# B166X.net
KiCad netlist of a schematic drawn in EAGLE
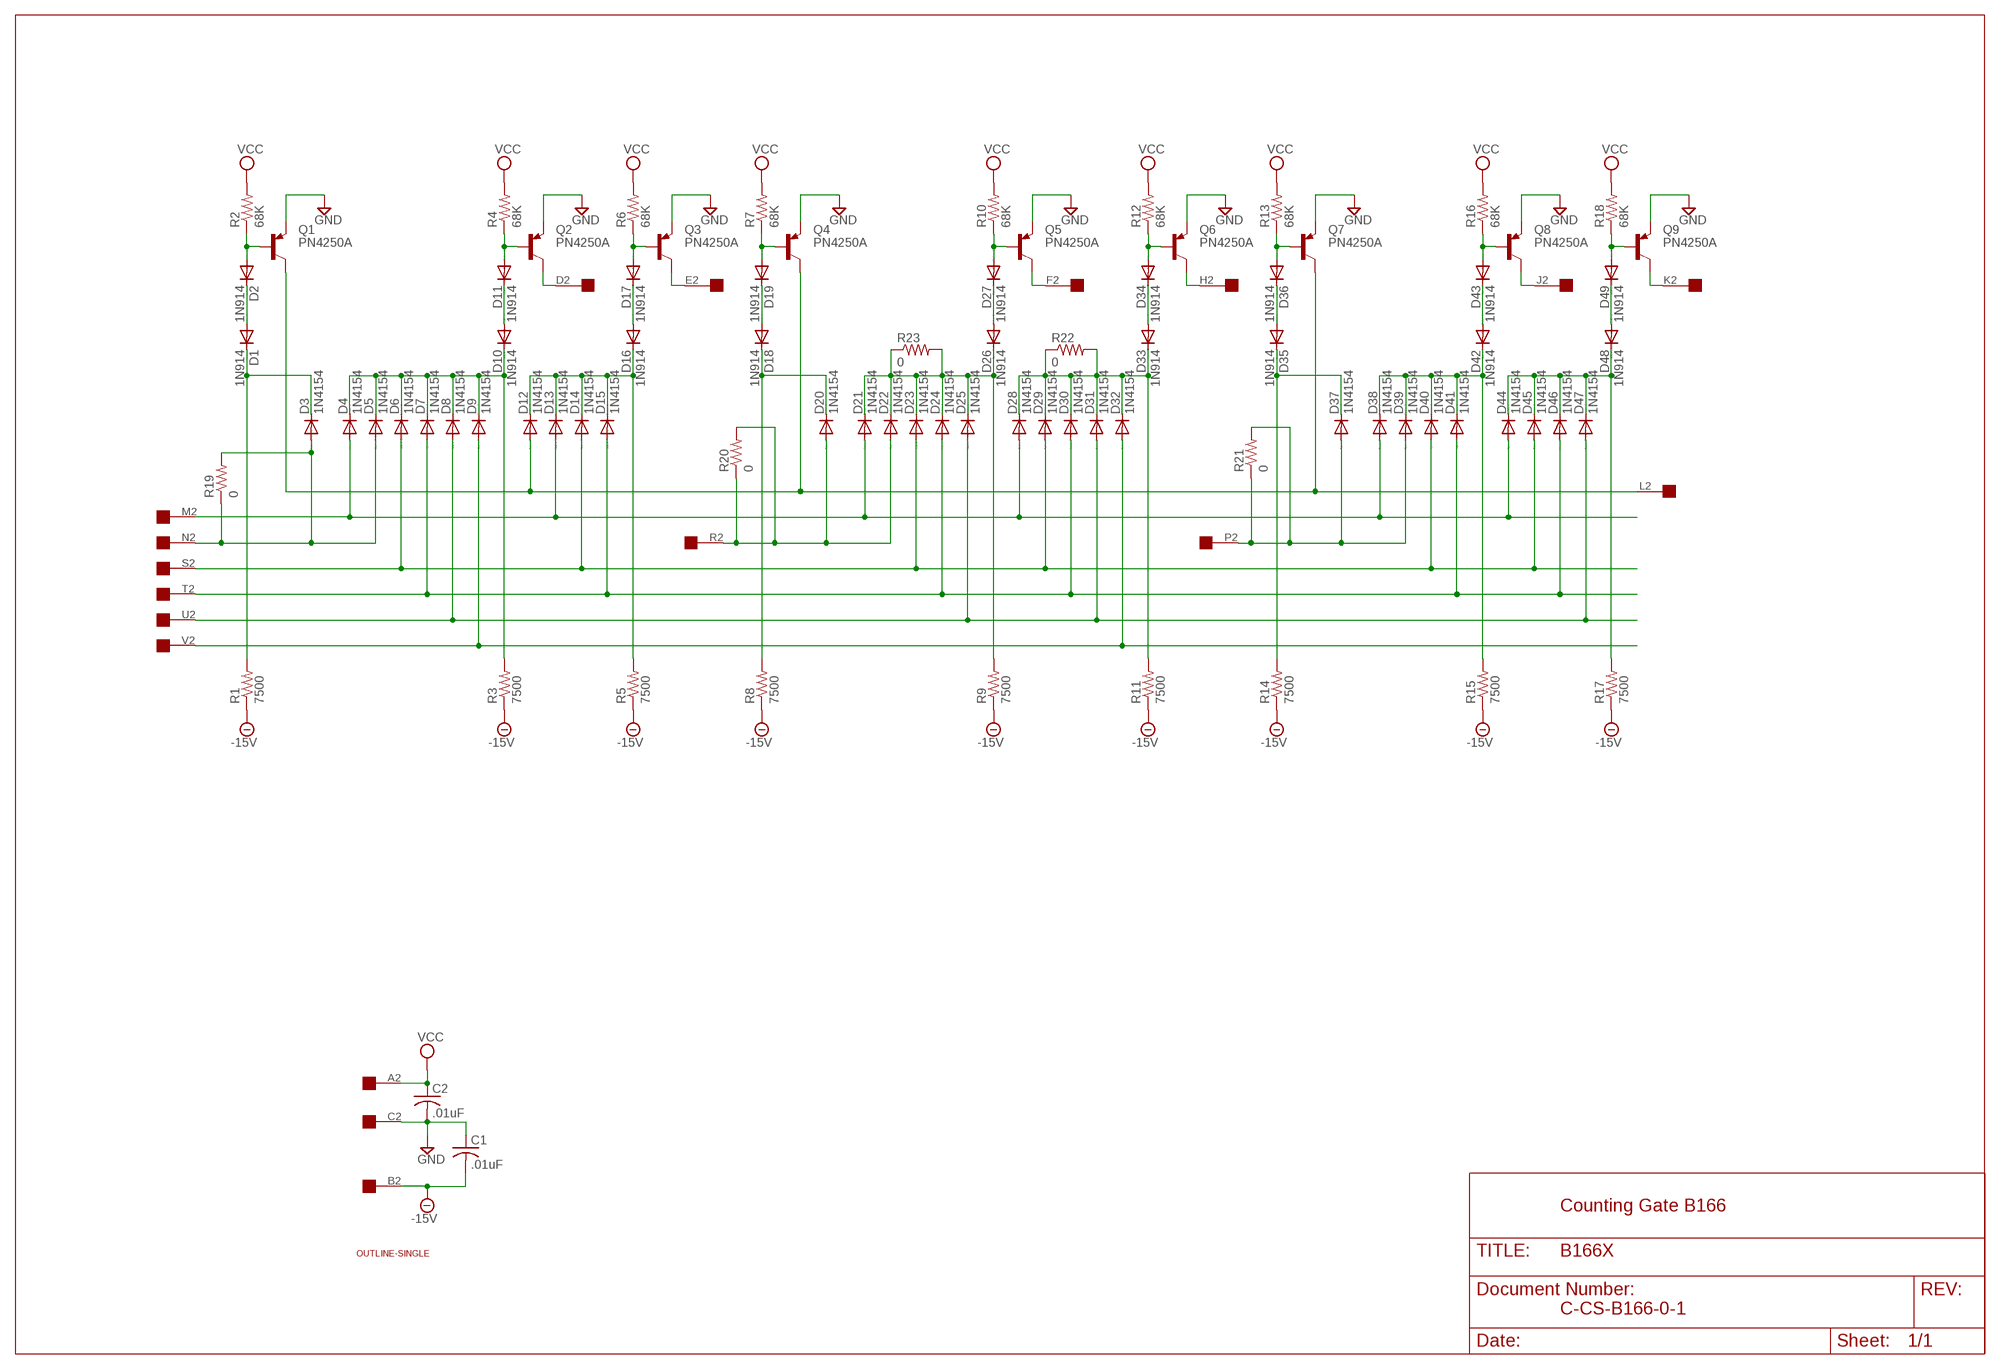
[diagram p0: schematic, sheet 1]

(export (version "E")
  (design (tool "Eeschema 10.0.6"))
  (components
    (comp (ref "C1")
      (value ".01uF")
      (footprint "eagle-import:C063-025X075")
      (libsource (lib "eagle-import") (part "C-US"))
    )
    (comp (ref "C2")
      (value ".01uF")
      (footprint "eagle-import:C063-025X075")
      (libsource (lib "eagle-import") (part "C-US"))
    )
    (comp (ref "D1")
      (value "1N914")
      (footprint "eagle-import:DO35-10")
      (libsource (lib "eagle-import") (part "DIODE-DO35-10"))
    )
    (comp (ref "D2")
      (value "1N914")
      (footprint "eagle-import:DO35-10")
      (libsource (lib "eagle-import") (part "DIODE-DO35-10"))
    )
    (comp (ref "D3")
      (value "1N4154")
      (footprint "eagle-import:DO35-10")
      (libsource (lib "eagle-import") (part "DIODE-DO35-10"))
    )
    (comp (ref "D4")
      (value "1N4154")
      (footprint "eagle-import:DO35-10")
      (libsource (lib "eagle-import") (part "DIODE-DO35-10"))
    )
    (comp (ref "D5")
      (value "1N4154")
      (footprint "eagle-import:DO35-10")
      (libsource (lib "eagle-import") (part "DIODE-DO35-10"))
    )
    (comp (ref "D6")
      (value "1N4154")
      (footprint "eagle-import:DO35-10")
      (libsource (lib "eagle-import") (part "DIODE-DO35-10"))
    )
    (comp (ref "D7")
      (value "1N4154")
      (footprint "eagle-import:DO35-10")
      (libsource (lib "eagle-import") (part "DIODE-DO35-10"))
    )
    (comp (ref "D8")
      (value "1N4154")
      (footprint "eagle-import:DO35-10")
      (libsource (lib "eagle-import") (part "DIODE-DO35-10"))
    )
    (comp (ref "D9")
      (value "1N4154")
      (footprint "eagle-import:DO35-10")
      (libsource (lib "eagle-import") (part "DIODE-DO35-10"))
    )
    (comp (ref "D10")
      (value "1N914")
      (footprint "eagle-import:DO35-10")
      (libsource (lib "eagle-import") (part "DIODE-DO35-10"))
    )
    (comp (ref "D11")
      (value "1N914")
      (footprint "eagle-import:DO35-10")
      (libsource (lib "eagle-import") (part "DIODE-DO35-10"))
    )
    (comp (ref "D12")
      (value "1N4154")
      (footprint "eagle-import:DO35-10")
      (libsource (lib "eagle-import") (part "DIODE-DO35-10"))
    )
    (comp (ref "D13")
      (value "1N4154")
      (footprint "eagle-import:DO35-10")
      (libsource (lib "eagle-import") (part "DIODE-DO35-10"))
    )
    (comp (ref "D14")
      (value "1N4154")
      (footprint "eagle-import:DO35-10")
      (libsource (lib "eagle-import") (part "DIODE-DO35-10"))
    )
    (comp (ref "D15")
      (value "1N4154")
      (footprint "eagle-import:DO35-10")
      (libsource (lib "eagle-import") (part "DIODE-DO35-10"))
    )
    (comp (ref "D16")
      (value "1N914")
      (footprint "eagle-import:DO35-10")
      (libsource (lib "eagle-import") (part "DIODE-DO35-10"))
    )
    (comp (ref "D17")
      (value "1N914")
      (footprint "eagle-import:DO35-10")
      (libsource (lib "eagle-import") (part "DIODE-DO35-10"))
    )
    (comp (ref "D18")
      (value "1N914")
      (footprint "eagle-import:DO35-10")
      (libsource (lib "eagle-import") (part "DIODE-DO35-10"))
    )
    (comp (ref "D19")
      (value "1N914")
      (footprint "eagle-import:DO35-10")
      (libsource (lib "eagle-import") (part "DIODE-DO35-10"))
    )
    (comp (ref "D20")
      (value "1N4154")
      (footprint "eagle-import:DO35-10")
      (libsource (lib "eagle-import") (part "DIODE-DO35-10"))
    )
    (comp (ref "D21")
      (value "1N4154")
      (footprint "eagle-import:DO35-10")
      (libsource (lib "eagle-import") (part "DIODE-DO35-10"))
    )
    (comp (ref "D22")
      (value "1N4154")
      (footprint "eagle-import:DO35-10")
      (libsource (lib "eagle-import") (part "DIODE-DO35-10"))
    )
    (comp (ref "D23")
      (value "1N4154")
      (footprint "eagle-import:DO35-10")
      (libsource (lib "eagle-import") (part "DIODE-DO35-10"))
    )
    (comp (ref "D24")
      (value "1N4154")
      (footprint "eagle-import:DO35-10")
      (libsource (lib "eagle-import") (part "DIODE-DO35-10"))
    )
    (comp (ref "D25")
      (value "1N4154")
      (footprint "eagle-import:DO35-10")
      (libsource (lib "eagle-import") (part "DIODE-DO35-10"))
    )
    (comp (ref "D26")
      (value "1N914")
      (footprint "eagle-import:DO35-10")
      (libsource (lib "eagle-import") (part "DIODE-DO35-10"))
    )
    (comp (ref "D27")
      (value "1N914")
      (footprint "eagle-import:DO35-10")
      (libsource (lib "eagle-import") (part "DIODE-DO35-10"))
    )
    (comp (ref "D28")
      (value "1N4154")
      (footprint "eagle-import:DO35-10")
      (libsource (lib "eagle-import") (part "DIODE-DO35-10"))
    )
    (comp (ref "D29")
      (value "1N4154")
      (footprint "eagle-import:DO35-10")
      (libsource (lib "eagle-import") (part "DIODE-DO35-10"))
    )
    (comp (ref "D30")
      (value "1N4154")
      (footprint "eagle-import:DO35-10")
      (libsource (lib "eagle-import") (part "DIODE-DO35-10"))
    )
    (comp (ref "D31")
      (value "1N4154")
      (footprint "eagle-import:DO35-10")
      (libsource (lib "eagle-import") (part "DIODE-DO35-10"))
    )
    (comp (ref "D32")
      (value "1N4154")
      (footprint "eagle-import:DO35-10")
      (libsource (lib "eagle-import") (part "DIODE-DO35-10"))
    )
    (comp (ref "D33")
      (value "1N914")
      (footprint "eagle-import:DO35-10")
      (libsource (lib "eagle-import") (part "DIODE-DO35-10"))
    )
    (comp (ref "D34")
      (value "1N914")
      (footprint "eagle-import:DO35-10")
      (libsource (lib "eagle-import") (part "DIODE-DO35-10"))
    )
    (comp (ref "D35")
      (value "1N914")
      (footprint "eagle-import:DO35-10")
      (libsource (lib "eagle-import") (part "DIODE-DO35-10"))
    )
    (comp (ref "D36")
      (value "1N914")
      (footprint "eagle-import:DO35-10")
      (libsource (lib "eagle-import") (part "DIODE-DO35-10"))
    )
    (comp (ref "D37")
      (value "1N4154")
      (footprint "eagle-import:DO35-10")
      (libsource (lib "eagle-import") (part "DIODE-DO35-10"))
    )
    (comp (ref "D38")
      (value "1N4154")
      (footprint "eagle-import:DO35-10")
      (libsource (lib "eagle-import") (part "DIODE-DO35-10"))
    )
    (comp (ref "D39")
      (value "1N4154")
      (footprint "eagle-import:DO35-10")
      (libsource (lib "eagle-import") (part "DIODE-DO35-10"))
    )
    (comp (ref "D40")
      (value "1N4154")
      (footprint "eagle-import:DO35-10")
      (libsource (lib "eagle-import") (part "DIODE-DO35-10"))
    )
    (comp (ref "D41")
      (value "1N4154")
      (footprint "eagle-import:DO35-10")
      (libsource (lib "eagle-import") (part "DIODE-DO35-10"))
    )
    (comp (ref "D42")
      (value "1N914")
      (footprint "eagle-import:DO35-10")
      (libsource (lib "eagle-import") (part "DIODE-DO35-10"))
    )
    (comp (ref "D43")
      (value "1N914")
      (footprint "eagle-import:DO35-10")
      (libsource (lib "eagle-import") (part "DIODE-DO35-10"))
    )
    (comp (ref "D44")
      (value "1N4154")
      (footprint "eagle-import:DO35-10")
      (libsource (lib "eagle-import") (part "DIODE-DO35-10"))
    )
    (comp (ref "D45")
      (value "1N4154")
      (footprint "eagle-import:DO35-10")
      (libsource (lib "eagle-import") (part "DIODE-DO35-10"))
    )
    (comp (ref "D46")
      (value "1N4154")
      (footprint "eagle-import:DO35-10")
      (libsource (lib "eagle-import") (part "DIODE-DO35-10"))
    )
    (comp (ref "D47")
      (value "1N4154")
      (footprint "eagle-import:DO35-10")
      (libsource (lib "eagle-import") (part "DIODE-DO35-10"))
    )
    (comp (ref "D48")
      (value "1N914")
      (footprint "eagle-import:DO35-10")
      (libsource (lib "eagle-import") (part "DIODE-DO35-10"))
    )
    (comp (ref "D49")
      (value "1N914")
      (footprint "eagle-import:DO35-10")
      (libsource (lib "eagle-import") (part "DIODE-DO35-10"))
    )
    (comp (ref "Q1")
      (value "PN4250A")
      (footprint "eagle-import:TO5")
      (libsource (lib "eagle-import") (part "-PNP-TO5"))
    )
    (comp (ref "Q2")
      (value "PN4250A")
      (footprint "eagle-import:TO5")
      (libsource (lib "eagle-import") (part "-PNP-TO5"))
    )
    (comp (ref "Q3")
      (value "PN4250A")
      (footprint "eagle-import:TO5")
      (libsource (lib "eagle-import") (part "-PNP-TO5"))
    )
    (comp (ref "Q4")
      (value "PN4250A")
      (footprint "eagle-import:TO5")
      (libsource (lib "eagle-import") (part "-PNP-TO5"))
    )
    (comp (ref "Q5")
      (value "PN4250A")
      (footprint "eagle-import:TO5")
      (libsource (lib "eagle-import") (part "-PNP-TO5"))
    )
    (comp (ref "Q6")
      (value "PN4250A")
      (footprint "eagle-import:TO5")
      (libsource (lib "eagle-import") (part "-PNP-TO5"))
    )
    (comp (ref "Q7")
      (value "PN4250A")
      (footprint "eagle-import:TO5")
      (libsource (lib "eagle-import") (part "-PNP-TO5"))
    )
    (comp (ref "Q8")
      (value "PN4250A")
      (footprint "eagle-import:TO5")
      (libsource (lib "eagle-import") (part "-PNP-TO5"))
    )
    (comp (ref "Q9")
      (value "PN4250A")
      (footprint "eagle-import:TO5")
      (libsource (lib "eagle-import") (part "-PNP-TO5"))
    )
    (comp (ref "R1")
      (value "7500")
      (footprint "eagle-import:0207_10")
      (libsource (lib "eagle-import") (part "R-US_0207/10"))
    )
    (comp (ref "R2")
      (value "68K")
      (footprint "eagle-import:0207_10")
      (libsource (lib "eagle-import") (part "R-US_0207/10"))
    )
    (comp (ref "R3")
      (value "7500")
      (footprint "eagle-import:0207_10")
      (libsource (lib "eagle-import") (part "R-US_0207/10"))
    )
    (comp (ref "R4")
      (value "68K")
      (footprint "eagle-import:0207_10")
      (libsource (lib "eagle-import") (part "R-US_0207/10"))
    )
    (comp (ref "R5")
      (value "7500")
      (footprint "eagle-import:0207_10")
      (libsource (lib "eagle-import") (part "R-US_0207/10"))
    )
    (comp (ref "R6")
      (value "68K")
      (footprint "eagle-import:0207_10")
      (libsource (lib "eagle-import") (part "R-US_0207/10"))
    )
    (comp (ref "R7")
      (value "68K")
      (footprint "eagle-import:0207_10")
      (libsource (lib "eagle-import") (part "R-US_0207/10"))
    )
    (comp (ref "R8")
      (value "7500")
      (footprint "eagle-import:0207_10")
      (libsource (lib "eagle-import") (part "R-US_0207/10"))
    )
    (comp (ref "R9")
      (value "7500")
      (footprint "eagle-import:0207_10")
      (libsource (lib "eagle-import") (part "R-US_0207/10"))
    )
    (comp (ref "R10")
      (value "68K")
      (footprint "eagle-import:0207_10")
      (libsource (lib "eagle-import") (part "R-US_0207/10"))
    )
    (comp (ref "R11")
      (value "7500")
      (footprint "eagle-import:0207_10")
      (libsource (lib "eagle-import") (part "R-US_0207/10"))
    )
    (comp (ref "R12")
      (value "68K")
      (footprint "eagle-import:0207_10")
      (libsource (lib "eagle-import") (part "R-US_0207/10"))
    )
    (comp (ref "R13")
      (value "68K")
      (footprint "eagle-import:0207_10")
      (libsource (lib "eagle-import") (part "R-US_0207/10"))
    )
    (comp (ref "R14")
      (value "7500")
      (footprint "eagle-import:0207_10")
      (libsource (lib "eagle-import") (part "R-US_0207/10"))
    )
    (comp (ref "R15")
      (value "7500")
      (footprint "eagle-import:0207_10")
      (libsource (lib "eagle-import") (part "R-US_0207/10"))
    )
    (comp (ref "R16")
      (value "68K")
      (footprint "eagle-import:0207_10")
      (libsource (lib "eagle-import") (part "R-US_0207/10"))
    )
    (comp (ref "R17")
      (value "7500")
      (footprint "eagle-import:0207_10")
      (libsource (lib "eagle-import") (part "R-US_0207/10"))
    )
    (comp (ref "R18")
      (value "68K")
      (footprint "eagle-import:0207_10")
      (libsource (lib "eagle-import") (part "R-US_0207/10"))
    )
    (comp (ref "R19")
      (value "0")
      (footprint "eagle-import:0207_10")
      (libsource (lib "eagle-import") (part "R-US_0207/10"))
    )
    (comp (ref "R20")
      (value "0")
      (footprint "eagle-import:0207_10")
      (libsource (lib "eagle-import") (part "R-US_0207/10"))
    )
    (comp (ref "R21")
      (value "0")
      (footprint "eagle-import:0207_10")
      (libsource (lib "eagle-import") (part "R-US_0207/10"))
    )
    (comp (ref "R22")
      (value "0")
      (footprint "eagle-import:0207_10")
      (libsource (lib "eagle-import") (part "R-US_0207/10"))
    )
    (comp (ref "R23")
      (value "0")
      (footprint "eagle-import:0207_10")
      (libsource (lib "eagle-import") (part "R-US_0207/10"))
    )
    (comp (ref "U$1")
      (value "OUTLINE-SINGLE")
      (footprint "eagle-import:SINGLE")
      (libsource (lib "eagle-import") (part "OUTLINE-SINGLE"))
    )
    (comp (ref "U$2")
      (value "EDGE-1")
      (footprint "eagle-import:EDGE-CON1")
      (libsource (lib "eagle-import") (part "EDGE-1"))
    )
  )
  (nets
    (net (code "1") (name "-15V") (class "Default")
      (node (ref "C1") (pin "2") (pinfunction "2_2") (pintype "passive"))
      (node (ref "R1") (pin "1") (pinfunction "1_1") (pintype "passive"))
      (node (ref "R11") (pin "1") (pinfunction "1_1") (pintype "passive"))
      (node (ref "R14") (pin "1") (pinfunction "1_1") (pintype "passive"))
      (node (ref "R15") (pin "1") (pinfunction "1_1") (pintype "passive"))
      (node (ref "R17") (pin "1") (pinfunction "1_1") (pintype "passive"))
      (node (ref "R3") (pin "1") (pinfunction "1_1") (pintype "passive"))
      (node (ref "R5") (pin "1") (pinfunction "1_1") (pintype "passive"))
      (node (ref "R8") (pin "1") (pinfunction "1_1") (pintype "passive"))
      (node (ref "R9") (pin "1") (pinfunction "1_1") (pintype "passive"))
      (node (ref "U$2") (pin "B2") (pinfunction "1_B2") (pintype "bidirectional"))
    )
    (net (code "2") (name "GND") (class "Default")
      (node (ref "C1") (pin "1") (pinfunction "1_1") (pintype "passive"))
      (node (ref "C2") (pin "2") (pinfunction "2_2") (pintype "passive"))
      (node (ref "Q1") (pin "1") (pinfunction "E_1") (pintype "passive"))
      (node (ref "Q2") (pin "1") (pinfunction "E_1") (pintype "passive"))
      (node (ref "Q3") (pin "1") (pinfunction "E_1") (pintype "passive"))
      (node (ref "Q4") (pin "1") (pinfunction "E_1") (pintype "passive"))
      (node (ref "Q5") (pin "1") (pinfunction "E_1") (pintype "passive"))
      (node (ref "Q6") (pin "1") (pinfunction "E_1") (pintype "passive"))
      (node (ref "Q7") (pin "1") (pinfunction "E_1") (pintype "passive"))
      (node (ref "Q8") (pin "1") (pinfunction "E_1") (pintype "passive"))
      (node (ref "Q9") (pin "1") (pinfunction "E_1") (pintype "passive"))
      (node (ref "U$2") (pin "C2") (pinfunction "1_C2") (pintype "bidirectional"))
    )
    (net (code "3") (name "Net-(D1-PadA)") (class "Default")
      (node (ref "D1") (pin "A") (pinfunction "A_A") (pintype "passive"))
      (node (ref "D2") (pin "C") (pinfunction "C_C") (pintype "passive"))
    )
    (net (code "4") (name "Net-(D1-PadC)") (class "Default")
      (node (ref "D1") (pin "C") (pinfunction "C_C") (pintype "passive"))
      (node (ref "D3") (pin "C") (pinfunction "C_C") (pintype "passive"))
      (node (ref "R1") (pin "2") (pinfunction "2_2") (pintype "passive"))
    )
    (net (code "5") (name "Net-(D10-PadA)") (class "Default")
      (node (ref "D10") (pin "A") (pinfunction "A_A") (pintype "passive"))
      (node (ref "D11") (pin "C") (pinfunction "C_C") (pintype "passive"))
    )
    (net (code "6") (name "Net-(D10-PadC)") (class "Default")
      (node (ref "D10") (pin "C") (pinfunction "C_C") (pintype "passive"))
      (node (ref "D4") (pin "C") (pinfunction "C_C") (pintype "passive"))
      (node (ref "D5") (pin "C") (pinfunction "C_C") (pintype "passive"))
      (node (ref "D6") (pin "C") (pinfunction "C_C") (pintype "passive"))
      (node (ref "D7") (pin "C") (pinfunction "C_C") (pintype "passive"))
      (node (ref "D8") (pin "C") (pinfunction "C_C") (pintype "passive"))
      (node (ref "D9") (pin "C") (pinfunction "C_C") (pintype "passive"))
      (node (ref "R3") (pin "2") (pinfunction "2_2") (pintype "passive"))
    )
    (net (code "7") (name "Net-(D12-PadC)") (class "Default")
      (node (ref "D12") (pin "C") (pinfunction "C_C") (pintype "passive"))
      (node (ref "D13") (pin "C") (pinfunction "C_C") (pintype "passive"))
      (node (ref "D14") (pin "C") (pinfunction "C_C") (pintype "passive"))
      (node (ref "D15") (pin "C") (pinfunction "C_C") (pintype "passive"))
      (node (ref "D16") (pin "C") (pinfunction "C_C") (pintype "passive"))
      (node (ref "R5") (pin "2") (pinfunction "2_2") (pintype "passive"))
    )
    (net (code "8") (name "Net-(D16-PadA)") (class "Default")
      (node (ref "D16") (pin "A") (pinfunction "A_A") (pintype "passive"))
      (node (ref "D17") (pin "C") (pinfunction "C_C") (pintype "passive"))
    )
    (net (code "9") (name "Net-(D18-PadA)") (class "Default")
      (node (ref "D18") (pin "A") (pinfunction "A_A") (pintype "passive"))
      (node (ref "D19") (pin "C") (pinfunction "C_C") (pintype "passive"))
    )
    (net (code "10") (name "Net-(D18-PadC)") (class "Default")
      (node (ref "D18") (pin "C") (pinfunction "C_C") (pintype "passive"))
      (node (ref "D20") (pin "C") (pinfunction "C_C") (pintype "passive"))
      (node (ref "R8") (pin "2") (pinfunction "2_2") (pintype "passive"))
    )
    (net (code "11") (name "Net-(D21-PadC)") (class "Default")
      (node (ref "D21") (pin "C") (pinfunction "C_C") (pintype "passive"))
      (node (ref "D22") (pin "C") (pinfunction "C_C") (pintype "passive"))
      (node (ref "D23") (pin "C") (pinfunction "C_C") (pintype "passive"))
      (node (ref "D24") (pin "C") (pinfunction "C_C") (pintype "passive"))
      (node (ref "D25") (pin "C") (pinfunction "C_C") (pintype "passive"))
      (node (ref "D26") (pin "C") (pinfunction "C_C") (pintype "passive"))
      (node (ref "R23") (pin "1") (pinfunction "1_1") (pintype "passive"))
      (node (ref "R23") (pin "2") (pinfunction "2_2") (pintype "passive"))
      (node (ref "R9") (pin "2") (pinfunction "2_2") (pintype "passive"))
    )
    (net (code "12") (name "Net-(D26-PadA)") (class "Default")
      (node (ref "D26") (pin "A") (pinfunction "A_A") (pintype "passive"))
      (node (ref "D27") (pin "C") (pinfunction "C_C") (pintype "passive"))
    )
    (net (code "13") (name "Net-(D28-PadC)") (class "Default")
      (node (ref "D28") (pin "C") (pinfunction "C_C") (pintype "passive"))
      (node (ref "D29") (pin "C") (pinfunction "C_C") (pintype "passive"))
      (node (ref "D30") (pin "C") (pinfunction "C_C") (pintype "passive"))
      (node (ref "D31") (pin "C") (pinfunction "C_C") (pintype "passive"))
      (node (ref "D32") (pin "C") (pinfunction "C_C") (pintype "passive"))
      (node (ref "D33") (pin "C") (pinfunction "C_C") (pintype "passive"))
      (node (ref "R11") (pin "2") (pinfunction "2_2") (pintype "passive"))
      (node (ref "R22") (pin "1") (pinfunction "1_1") (pintype "passive"))
      (node (ref "R22") (pin "2") (pinfunction "2_2") (pintype "passive"))
    )
    (net (code "14") (name "Net-(D33-PadA)") (class "Default")
      (node (ref "D33") (pin "A") (pinfunction "A_A") (pintype "passive"))
      (node (ref "D34") (pin "C") (pinfunction "C_C") (pintype "passive"))
    )
    (net (code "15") (name "Net-(D35-PadA)") (class "Default")
      (node (ref "D35") (pin "A") (pinfunction "A_A") (pintype "passive"))
      (node (ref "D36") (pin "C") (pinfunction "C_C") (pintype "passive"))
    )
    (net (code "16") (name "Net-(D35-PadC)") (class "Default")
      (node (ref "D35") (pin "C") (pinfunction "C_C") (pintype "passive"))
      (node (ref "D37") (pin "C") (pinfunction "C_C") (pintype "passive"))
      (node (ref "R14") (pin "2") (pinfunction "2_2") (pintype "passive"))
    )
    (net (code "17") (name "Net-(D38-PadC)") (class "Default")
      (node (ref "D38") (pin "C") (pinfunction "C_C") (pintype "passive"))
      (node (ref "D39") (pin "C") (pinfunction "C_C") (pintype "passive"))
      (node (ref "D40") (pin "C") (pinfunction "C_C") (pintype "passive"))
      (node (ref "D41") (pin "C") (pinfunction "C_C") (pintype "passive"))
      (node (ref "D42") (pin "C") (pinfunction "C_C") (pintype "passive"))
      (node (ref "R15") (pin "2") (pinfunction "2_2") (pintype "passive"))
    )
    (net (code "18") (name "Net-(D42-PadA)") (class "Default")
      (node (ref "D42") (pin "A") (pinfunction "A_A") (pintype "passive"))
      (node (ref "D43") (pin "C") (pinfunction "C_C") (pintype "passive"))
    )
    (net (code "19") (name "Net-(D44-PadC)") (class "Default")
      (node (ref "D44") (pin "C") (pinfunction "C_C") (pintype "passive"))
      (node (ref "D45") (pin "C") (pinfunction "C_C") (pintype "passive"))
      (node (ref "D46") (pin "C") (pinfunction "C_C") (pintype "passive"))
      (node (ref "D47") (pin "C") (pinfunction "C_C") (pintype "passive"))
      (node (ref "D48") (pin "C") (pinfunction "C_C") (pintype "passive"))
      (node (ref "R17") (pin "2") (pinfunction "2_2") (pintype "passive"))
    )
    (net (code "20") (name "Net-(D48-PadA)") (class "Default")
      (node (ref "D48") (pin "A") (pinfunction "A_A") (pintype "passive"))
      (node (ref "D49") (pin "C") (pinfunction "C_C") (pintype "passive"))
    )
    (net (code "21") (name "Net-(Q1-B)") (class "Default")
      (node (ref "D2") (pin "A") (pinfunction "A_A") (pintype "passive"))
      (node (ref "Q1") (pin "2") (pinfunction "B_2") (pintype "passive"))
      (node (ref "R2") (pin "1") (pinfunction "1_1") (pintype "passive"))
    )
    (net (code "22") (name "Net-(Q1-C)") (class "Default")
      (node (ref "D12") (pin "A") (pinfunction "A_A") (pintype "passive"))
      (node (ref "Q1") (pin "3") (pinfunction "C_3") (pintype "passive"))
      (node (ref "Q4") (pin "3") (pinfunction "C_3") (pintype "passive"))
      (node (ref "Q7") (pin "3") (pinfunction "C_3") (pintype "passive"))
      (node (ref "U$2") (pin "L2") (pinfunction "1_L2") (pintype "bidirectional"))
    )
    (net (code "23") (name "Net-(Q2-B)") (class "Default")
      (node (ref "D11") (pin "A") (pinfunction "A_A") (pintype "passive"))
      (node (ref "Q2") (pin "2") (pinfunction "B_2") (pintype "passive"))
      (node (ref "R4") (pin "1") (pinfunction "1_1") (pintype "passive"))
    )
    (net (code "24") (name "Net-(Q2-C)") (class "Default")
      (node (ref "Q2") (pin "3") (pinfunction "C_3") (pintype "passive"))
      (node (ref "U$2") (pin "D2") (pinfunction "1_D2") (pintype "bidirectional"))
    )
    (net (code "25") (name "Net-(Q3-B)") (class "Default")
      (node (ref "D17") (pin "A") (pinfunction "A_A") (pintype "passive"))
      (node (ref "Q3") (pin "2") (pinfunction "B_2") (pintype "passive"))
      (node (ref "R6") (pin "1") (pinfunction "1_1") (pintype "passive"))
    )
    (net (code "26") (name "Net-(Q3-C)") (class "Default")
      (node (ref "Q3") (pin "3") (pinfunction "C_3") (pintype "passive"))
      (node (ref "U$2") (pin "E2") (pinfunction "1_E2") (pintype "bidirectional"))
    )
    (net (code "27") (name "Net-(Q4-B)") (class "Default")
      (node (ref "D19") (pin "A") (pinfunction "A_A") (pintype "passive"))
      (node (ref "Q4") (pin "2") (pinfunction "B_2") (pintype "passive"))
      (node (ref "R7") (pin "1") (pinfunction "1_1") (pintype "passive"))
    )
    (net (code "28") (name "Net-(Q5-B)") (class "Default")
      (node (ref "D27") (pin "A") (pinfunction "A_A") (pintype "passive"))
      (node (ref "Q5") (pin "2") (pinfunction "B_2") (pintype "passive"))
      (node (ref "R10") (pin "1") (pinfunction "1_1") (pintype "passive"))
    )
    (net (code "29") (name "Net-(Q5-C)") (class "Default")
      (node (ref "Q5") (pin "3") (pinfunction "C_3") (pintype "passive"))
      (node (ref "U$2") (pin "F2") (pinfunction "1_F2") (pintype "bidirectional"))
    )
    (net (code "30") (name "Net-(Q6-B)") (class "Default")
      (node (ref "D34") (pin "A") (pinfunction "A_A") (pintype "passive"))
      (node (ref "Q6") (pin "2") (pinfunction "B_2") (pintype "passive"))
      (node (ref "R12") (pin "1") (pinfunction "1_1") (pintype "passive"))
    )
    (net (code "31") (name "Net-(Q6-C)") (class "Default")
      (node (ref "Q6") (pin "3") (pinfunction "C_3") (pintype "passive"))
      (node (ref "U$2") (pin "H2") (pinfunction "1_H2") (pintype "bidirectional"))
    )
    (net (code "32") (name "Net-(Q7-B)") (class "Default")
      (node (ref "D36") (pin "A") (pinfunction "A_A") (pintype "passive"))
      (node (ref "Q7") (pin "2") (pinfunction "B_2") (pintype "passive"))
      (node (ref "R13") (pin "1") (pinfunction "1_1") (pintype "passive"))
    )
    (net (code "33") (name "Net-(Q8-B)") (class "Default")
      (node (ref "D43") (pin "A") (pinfunction "A_A") (pintype "passive"))
      (node (ref "Q8") (pin "2") (pinfunction "B_2") (pintype "passive"))
      (node (ref "R16") (pin "1") (pinfunction "1_1") (pintype "passive"))
    )
    (net (code "34") (name "Net-(Q8-C)") (class "Default")
      (node (ref "Q8") (pin "3") (pinfunction "C_3") (pintype "passive"))
      (node (ref "U$2") (pin "J2") (pinfunction "1_J2") (pintype "bidirectional"))
    )
    (net (code "35") (name "Net-(Q9-B)") (class "Default")
      (node (ref "D49") (pin "A") (pinfunction "A_A") (pintype "passive"))
      (node (ref "Q9") (pin "2") (pinfunction "B_2") (pintype "passive"))
      (node (ref "R18") (pin "1") (pinfunction "1_1") (pintype "passive"))
    )
    (net (code "36") (name "Net-(Q9-C)") (class "Default")
      (node (ref "Q9") (pin "3") (pinfunction "C_3") (pintype "passive"))
      (node (ref "U$2") (pin "K2") (pinfunction "1_K2") (pintype "bidirectional"))
    )
    (net (code "37") (name "Net-(U$2K-1)") (class "Default")
      (node (ref "D13") (pin "A") (pinfunction "A_A") (pintype "passive"))
      (node (ref "D21") (pin "A") (pinfunction "A_A") (pintype "passive"))
      (node (ref "D28") (pin "A") (pinfunction "A_A") (pintype "passive"))
      (node (ref "D38") (pin "A") (pinfunction "A_A") (pintype "passive"))
      (node (ref "D4") (pin "A") (pinfunction "A_A") (pintype "passive"))
      (node (ref "D44") (pin "A") (pinfunction "A_A") (pintype "passive"))
      (node (ref "U$2") (pin "M2") (pinfunction "1_M2") (pintype "bidirectional"))
    )
    (net (code "38") (name "Net-(U$2L-1)") (class "Default")
      (node (ref "D3") (pin "A") (pinfunction "A_A") (pintype "passive"))
      (node (ref "D5") (pin "A") (pinfunction "A_A") (pintype "passive"))
      (node (ref "R19") (pin "1") (pinfunction "1_1") (pintype "passive"))
      (node (ref "R19") (pin "2") (pinfunction "2_2") (pintype "passive"))
      (node (ref "U$2") (pin "N2") (pinfunction "1_N2") (pintype "bidirectional"))
    )
    (net (code "39") (name "Net-(U$2M-1)") (class "Default")
      (node (ref "D37") (pin "A") (pinfunction "A_A") (pintype "passive"))
      (node (ref "D39") (pin "A") (pinfunction "A_A") (pintype "passive"))
      (node (ref "R21") (pin "1") (pinfunction "1_1") (pintype "passive"))
      (node (ref "R21") (pin "2") (pinfunction "2_2") (pintype "passive"))
      (node (ref "U$2") (pin "P2") (pinfunction "1_P2") (pintype "bidirectional"))
    )
    (net (code "40") (name "Net-(U$2N-1)") (class "Default")
      (node (ref "D20") (pin "A") (pinfunction "A_A") (pintype "passive"))
      (node (ref "D22") (pin "A") (pinfunction "A_A") (pintype "passive"))
      (node (ref "R20") (pin "1") (pinfunction "1_1") (pintype "passive"))
      (node (ref "R20") (pin "2") (pinfunction "2_2") (pintype "passive"))
      (node (ref "U$2") (pin "R2") (pinfunction "1_R2") (pintype "bidirectional"))
    )
    (net (code "41") (name "Net-(U$2O-1)") (class "Default")
      (node (ref "D14") (pin "A") (pinfunction "A_A") (pintype "passive"))
      (node (ref "D23") (pin "A") (pinfunction "A_A") (pintype "passive"))
      (node (ref "D29") (pin "A") (pinfunction "A_A") (pintype "passive"))
      (node (ref "D40") (pin "A") (pinfunction "A_A") (pintype "passive"))
      (node (ref "D45") (pin "A") (pinfunction "A_A") (pintype "passive"))
      (node (ref "D6") (pin "A") (pinfunction "A_A") (pintype "passive"))
      (node (ref "U$2") (pin "S2") (pinfunction "1_S2") (pintype "bidirectional"))
    )
    (net (code "42") (name "Net-(U$2P-1)") (class "Default")
      (node (ref "D15") (pin "A") (pinfunction "A_A") (pintype "passive"))
      (node (ref "D24") (pin "A") (pinfunction "A_A") (pintype "passive"))
      (node (ref "D30") (pin "A") (pinfunction "A_A") (pintype "passive"))
      (node (ref "D41") (pin "A") (pinfunction "A_A") (pintype "passive"))
      (node (ref "D46") (pin "A") (pinfunction "A_A") (pintype "passive"))
      (node (ref "D7") (pin "A") (pinfunction "A_A") (pintype "passive"))
      (node (ref "U$2") (pin "T2") (pinfunction "1_T2") (pintype "bidirectional"))
    )
    (net (code "43") (name "Net-(U$2Q-1)") (class "Default")
      (node (ref "D25") (pin "A") (pinfunction "A_A") (pintype "passive"))
      (node (ref "D31") (pin "A") (pinfunction "A_A") (pintype "passive"))
      (node (ref "D47") (pin "A") (pinfunction "A_A") (pintype "passive"))
      (node (ref "D8") (pin "A") (pinfunction "A_A") (pintype "passive"))
      (node (ref "U$2") (pin "U2") (pinfunction "1_U2") (pintype "bidirectional"))
    )
    (net (code "44") (name "Net-(U$2R-1)") (class "Default")
      (node (ref "D32") (pin "A") (pinfunction "A_A") (pintype "passive"))
      (node (ref "D9") (pin "A") (pinfunction "A_A") (pintype "passive"))
      (node (ref "U$2") (pin "V2") (pinfunction "1_V2") (pintype "bidirectional"))
    )
    (net (code "45") (name "VCC") (class "Default")
      (node (ref "C2") (pin "1") (pinfunction "1_1") (pintype "passive"))
      (node (ref "R10") (pin "2") (pinfunction "2_2") (pintype "passive"))
      (node (ref "R12") (pin "2") (pinfunction "2_2") (pintype "passive"))
      (node (ref "R13") (pin "2") (pinfunction "2_2") (pintype "passive"))
      (node (ref "R16") (pin "2") (pinfunction "2_2") (pintype "passive"))
      (node (ref "R18") (pin "2") (pinfunction "2_2") (pintype "passive"))
      (node (ref "R2") (pin "2") (pinfunction "2_2") (pintype "passive"))
      (node (ref "R4") (pin "2") (pinfunction "2_2") (pintype "passive"))
      (node (ref "R6") (pin "2") (pinfunction "2_2") (pintype "passive"))
      (node (ref "R7") (pin "2") (pinfunction "2_2") (pintype "passive"))
      (node (ref "U$2") (pin "A2") (pinfunction "1_A2") (pintype "bidirectional"))
    )
  )
)
